# Data.net
KiCad netlist of a schematic drawn in Altium Designer
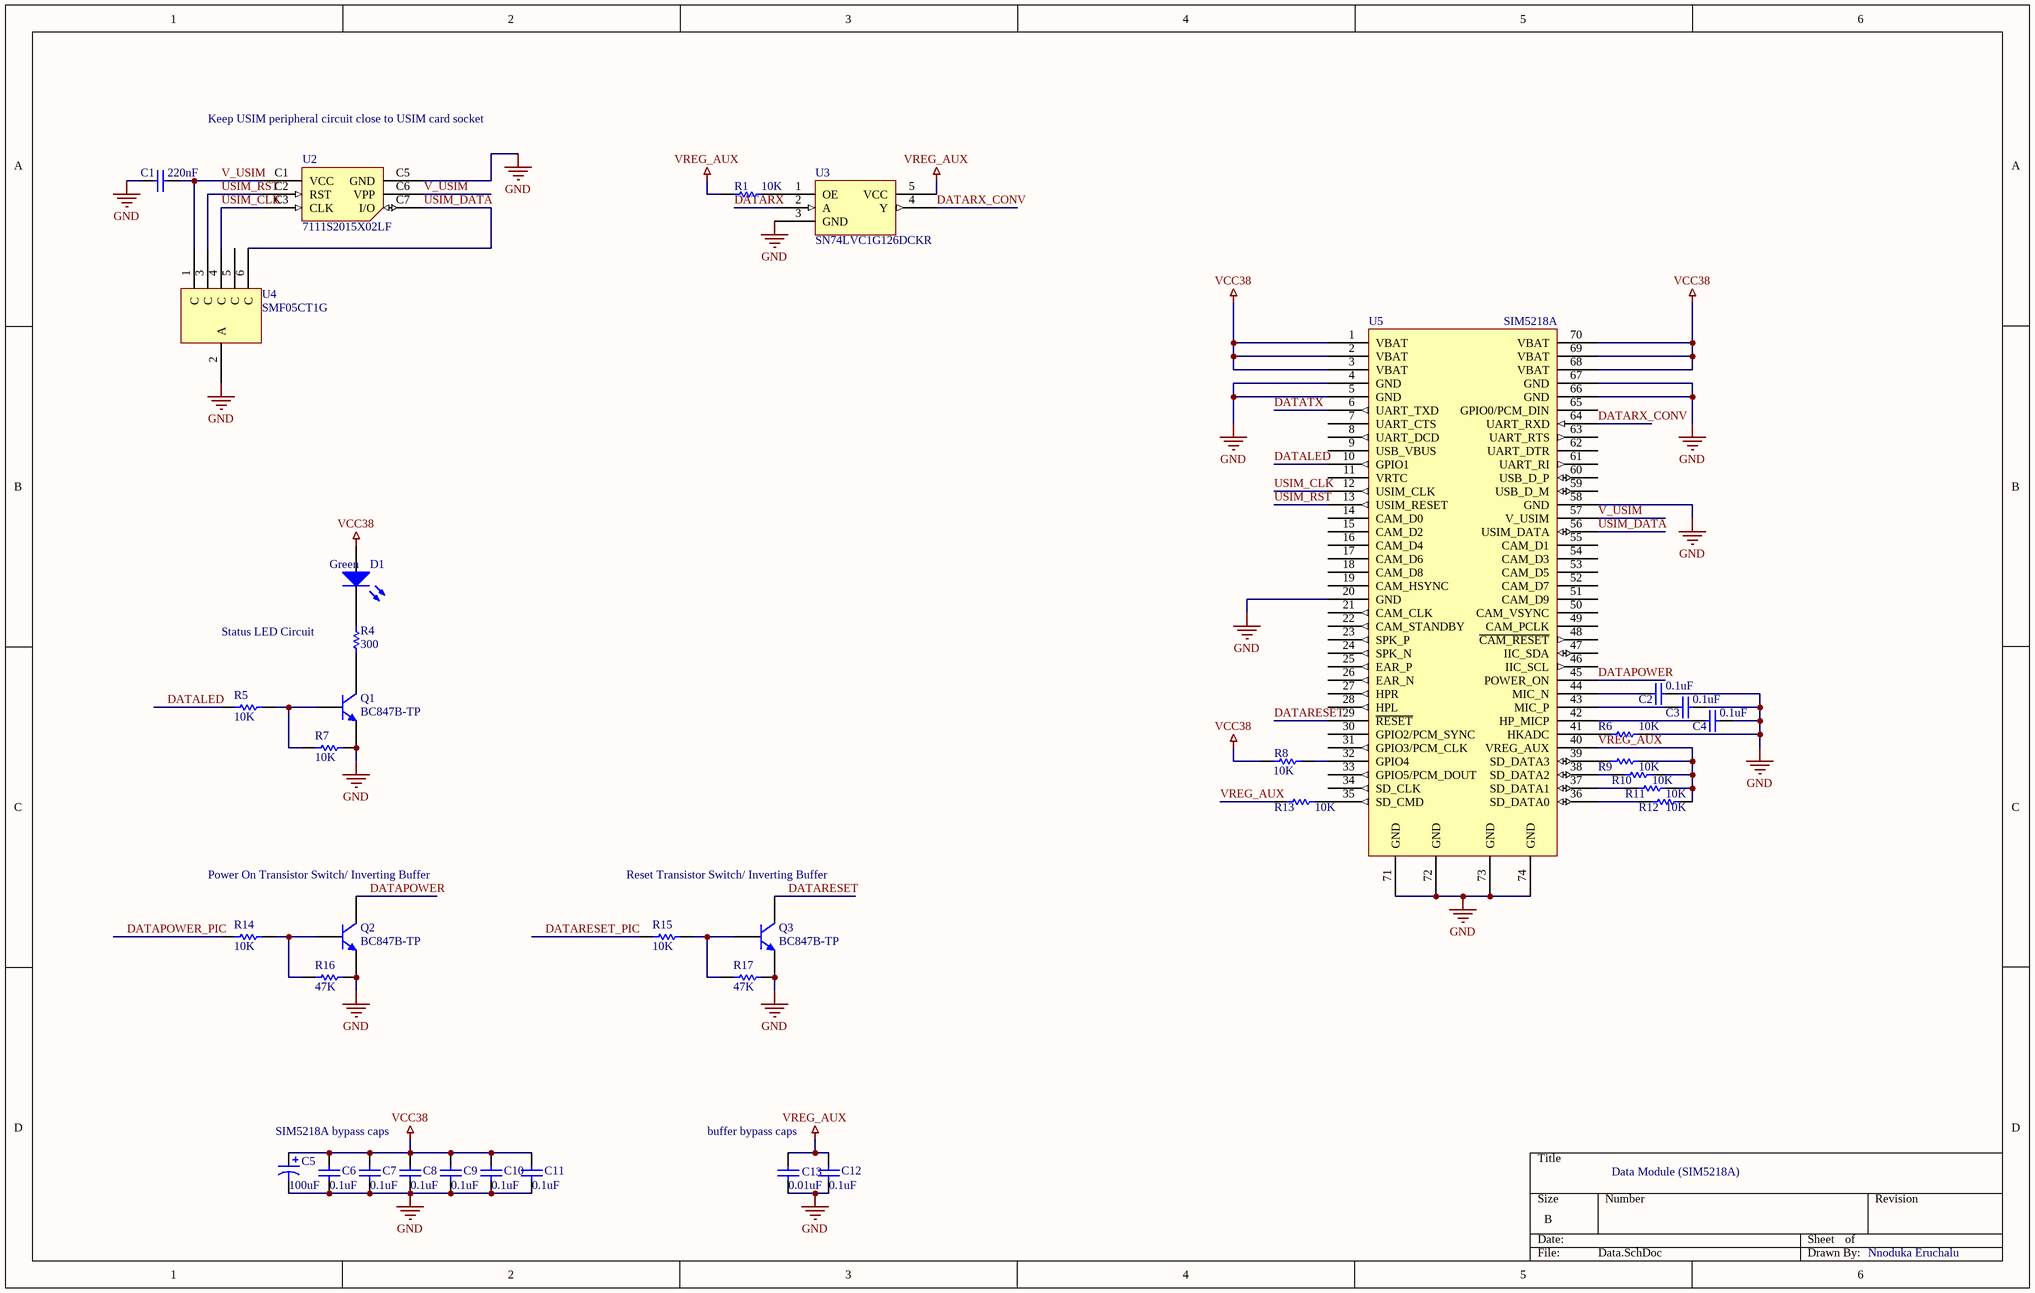
[diagram p0: Data.SchDoc]

(export (version "E")
  (design (tool "Eeschema 10.0.6"))
  (components
    (comp (ref "C1")
      (value "220nF")
      (footprint "2012[0805]")
      (description "Ceramic Chip Capacitor - Standard")
      (fields (field (name "Comment") "C2012X7R1H224K") (field (name "PUBLISHER") "Altium Limited"))
      (libsource (lib "KEMET Chip Capacitor") (part "C0805"))
    )
    (comp (ref "C2")
      (value "0.1uF")
      (footprint "2012[0805]")
      (description "Ceramic Chip Capacitor - Standard")
      (fields (field (name "Comment") "C2012X7R1H104K/0.85") (field (name "PUBLISHER") "Altium Limited"))
      (libsource (lib "KEMET Chip Capacitor") (part "C0805"))
    )
    (comp (ref "C3")
      (value "0.1uF")
      (footprint "2012[0805]")
      (description "Ceramic Chip Capacitor - Standard")
      (fields (field (name "Comment") "C2012X7R1H104K/0.85") (field (name "PUBLISHER") "Altium Limited"))
      (libsource (lib "KEMET Chip Capacitor") (part "C0805"))
    )
    (comp (ref "C4")
      (value "0.1uF")
      (footprint "2012[0805]")
      (description "Ceramic Chip Capacitor - Standard")
      (fields (field (name "Comment") "C2012X7R1H104K/0.85") (field (name "PUBLISHER") "Altium Limited"))
      (libsource (lib "KEMET Chip Capacitor") (part "C0805"))
    )
    (comp (ref "C5")
      (value "100uF")
      (footprint "easypay:TC3528-1411")
      (description "Polarized Capacitor (Radial)")
      (fields (field (name "Comment") "T520B107M004ATE070") (field (name "PUBLISHER") "Altium Limited"))
      (libsource (lib "Miscellaneous Devices") (part "Cap Pol1"))
    )
    (comp (ref "C6")
      (value "0.1uF")
      (footprint "2012[0805]")
      (description "Ceramic Chip Capacitor - Standard")
      (fields (field (name "Comment") "C2012X7R1H104K/0.85") (field (name "PUBLISHER") "Altium Limited"))
      (libsource (lib "KEMET Chip Capacitor") (part "C0805"))
    )
    (comp (ref "C7")
      (value "0.1uF")
      (footprint "2012[0805]")
      (description "Ceramic Chip Capacitor - Standard")
      (fields (field (name "Comment") "C2012X7R1H104K/0.85") (field (name "PUBLISHER") "Altium Limited"))
      (libsource (lib "KEMET Chip Capacitor") (part "C0805"))
    )
    (comp (ref "C8")
      (value "0.1uF")
      (footprint "2012[0805]")
      (description "Ceramic Chip Capacitor - Standard")
      (fields (field (name "Comment") "C2012X7R1H104K/0.85") (field (name "PUBLISHER") "Altium Limited"))
      (libsource (lib "KEMET Chip Capacitor") (part "C0805"))
    )
    (comp (ref "C9")
      (value "0.1uF")
      (footprint "2012[0805]")
      (description "Ceramic Chip Capacitor - Standard")
      (fields (field (name "Comment") "C2012X7R1H104K/0.85") (field (name "PUBLISHER") "Altium Limited"))
      (libsource (lib "KEMET Chip Capacitor") (part "C0805"))
    )
    (comp (ref "C10")
      (value "0.1uF")
      (footprint "2012[0805]")
      (description "Ceramic Chip Capacitor - Standard")
      (fields (field (name "Comment") "C2012X7R1H104K/0.85") (field (name "PUBLISHER") "Altium Limited"))
      (libsource (lib "KEMET Chip Capacitor") (part "C0805"))
    )
    (comp (ref "C11")
      (value "0.1uF")
      (footprint "2012[0805]")
      (description "Ceramic Chip Capacitor - Standard")
      (fields (field (name "Comment") "C2012X7R1H104K/0.85") (field (name "PUBLISHER") "Altium Limited"))
      (libsource (lib "KEMET Chip Capacitor") (part "C0805"))
    )
    (comp (ref "C12")
      (value "0.1uF")
      (footprint "2012[0805]")
      (description "Ceramic Chip Capacitor - Standard")
      (fields (field (name "Comment") "C2012X7R1H104K/0.85") (field (name "PUBLISHER") "Altium Limited"))
      (libsource (lib "KEMET Chip Capacitor") (part "C0805"))
    )
    (comp (ref "C13")
      (value "0.01uF")
      (footprint "2012[0805]")
      (description "Ceramic Chip Capacitor - Standard")
      (fields (field (name "Comment") "C2012X7R2E103K") (field (name "PUBLISHER") "Altium Limited"))
      (libsource (lib "KEMET Chip Capacitor") (part "C0805"))
    )
    (comp (ref "D1")
      (value "Green")
      (footprint "LTST-C17X")
      (description "Typical RED, GREEN, YELLOW, AMBER GaAs LED")
      (fields (field (name "Comment") "LTST-C171GKT") (field (name "PUBLISHER") "Altium Limited"))
      (libsource (lib "Miscellaneous Devices") (part "LED2"))
    )
    (comp (ref "Q1")
      (value "BC847B-TP")
      (footprint "SOT23-3N")
      (description "NPN Bipolar Transistor")
      (fields (field (name "PUBLISHER") "Altium Limited"))
      (libsource (lib "Miscellaneous Devices") (part "NPN"))
    )
    (comp (ref "Q2")
      (value "BC847B-TP")
      (footprint "SOT23-3N")
      (description "NPN Bipolar Transistor")
      (fields (field (name "PUBLISHER") "Altium Limited"))
      (libsource (lib "Miscellaneous Devices") (part "NPN"))
    )
    (comp (ref "Q3")
      (value "BC847B-TP")
      (footprint "SOT23-3N")
      (description "NPN Bipolar Transistor")
      (fields (field (name "PUBLISHER") "Altium Limited"))
      (libsource (lib "Miscellaneous Devices") (part "NPN"))
    )
    (comp (ref "R1")
      (value "10K")
      (footprint "Miscellaneous Devices:2012[0805]")
      (description "Resistor")
      (fields (field (name "Comment") "ERJ-6GEYJ103V") (field (name "PUBLISHER") "Altium Limited"))
      (libsource (lib "Miscellaneous Devices") (part "Res1"))
    )
    (comp (ref "R4")
      (value "300")
      (footprint "Miscellaneous Devices:2012[0805]")
      (description "Resistor")
      (fields (field (name "Comment") "ERJ-6GEYJ301V") (field (name "PUBLISHER") "Altium Limited"))
      (libsource (lib "Miscellaneous Devices") (part "Res1"))
    )
    (comp (ref "R5")
      (value "10K")
      (footprint "Miscellaneous Devices:2012[0805]")
      (description "Resistor")
      (fields (field (name "Comment") "ERJ-6GEYJ103V") (field (name "PUBLISHER") "Altium Limited"))
      (libsource (lib "Miscellaneous Devices") (part "Res1"))
    )
    (comp (ref "R6")
      (value "10K")
      (footprint "Miscellaneous Devices:2012[0805]")
      (description "Resistor")
      (fields (field (name "Comment") "ERJ-6GEYJ103V") (field (name "PUBLISHER") "Altium Limited"))
      (libsource (lib "Miscellaneous Devices") (part "Res1"))
    )
    (comp (ref "R7")
      (value "10K")
      (footprint "Miscellaneous Devices:2012[0805]")
      (description "Resistor")
      (fields (field (name "Comment") "ERJ-6GEYJ103V") (field (name "PUBLISHER") "Altium Limited"))
      (libsource (lib "Miscellaneous Devices") (part "Res1"))
    )
    (comp (ref "R8")
      (value "10K")
      (footprint "Miscellaneous Devices:2012[0805]")
      (description "Resistor")
      (fields (field (name "Comment") "ERJ-6GEYJ103V") (field (name "PUBLISHER") "Altium Limited"))
      (libsource (lib "Miscellaneous Devices") (part "Res1"))
    )
    (comp (ref "R9")
      (value "10K")
      (footprint "Miscellaneous Devices:2012[0805]")
      (description "Resistor")
      (fields (field (name "Comment") "ERJ-6GEYJ103V") (field (name "PUBLISHER") "Altium Limited"))
      (libsource (lib "Miscellaneous Devices") (part "Res1"))
    )
    (comp (ref "R10")
      (value "10K")
      (footprint "Miscellaneous Devices:2012[0805]")
      (description "Resistor")
      (fields (field (name "Comment") "ERJ-6GEYJ103V") (field (name "PUBLISHER") "Altium Limited"))
      (libsource (lib "Miscellaneous Devices") (part "Res1"))
    )
    (comp (ref "R11")
      (value "10K")
      (footprint "Miscellaneous Devices:2012[0805]")
      (description "Resistor")
      (fields (field (name "Comment") "ERJ-6GEYJ103V") (field (name "PUBLISHER") "Altium Limited"))
      (libsource (lib "Miscellaneous Devices") (part "Res1"))
    )
    (comp (ref "R12")
      (value "10K")
      (footprint "Miscellaneous Devices:2012[0805]")
      (description "Resistor")
      (fields (field (name "Comment") "ERJ-6GEYJ103V") (field (name "PUBLISHER") "Altium Limited"))
      (libsource (lib "Miscellaneous Devices") (part "Res1"))
    )
    (comp (ref "R13")
      (value "10K")
      (footprint "Miscellaneous Devices:2012[0805]")
      (description "Resistor")
      (fields (field (name "Comment") "ERJ-6GEYJ103V") (field (name "PUBLISHER") "Altium Limited"))
      (libsource (lib "Miscellaneous Devices") (part "Res1"))
    )
    (comp (ref "R14")
      (value "10K")
      (footprint "Miscellaneous Devices:2012[0805]")
      (description "Resistor")
      (fields (field (name "Comment") "ERJ-6GEYJ103V") (field (name "PUBLISHER") "Altium Limited"))
      (libsource (lib "Miscellaneous Devices") (part "Res1"))
    )
    (comp (ref "R15")
      (value "10K")
      (footprint "Miscellaneous Devices:2012[0805]")
      (description "Resistor")
      (fields (field (name "Comment") "ERJ-6GEYJ103V") (field (name "PUBLISHER") "Altium Limited"))
      (libsource (lib "Miscellaneous Devices") (part "Res1"))
    )
    (comp (ref "R16")
      (value "47K")
      (footprint "Miscellaneous Devices:2012[0805]")
      (description "Resistor")
      (fields (field (name "Comment") "ERJ-6GEYJ473V") (field (name "PUBLISHER") "Altium Limited"))
      (libsource (lib "Miscellaneous Devices") (part "Res1"))
    )
    (comp (ref "R17")
      (value "47K")
      (footprint "Miscellaneous Devices:2012[0805]")
      (description "Resistor")
      (fields (field (name "Comment") "ERJ-6GEYJ473V") (field (name "PUBLISHER") "Altium Limited"))
      (libsource (lib "Miscellaneous Devices") (part "Res1"))
    )
    (comp (ref "U2")
      (value "7111S2015X02LF")
      (footprint "7111S2015X02LF")
      (libsource (lib "easypay") (part "7111S2015X02LF"))
    )
    (comp (ref "U3")
      (value "SN74LVC1G126DCKR")
      (footprint "SOT353-5N")
      (libsource (lib "easypay") (part "SN74LVC1G126"))
    )
    (comp (ref "U4") (value "SMF05CT1G") (footprint "SOT363-6N") (libsource (lib "easypay") (part "SMF05C")))
    (comp (ref "U5")
      (value "SIM5218A")
      (footprint "SIM5218A v2")
      (libsource (lib "easypay") (part "SIM5218A"))
    )
  )
  (nets
    (net (code "1") (name "/DATALED") (class "Default")
      (node (ref "R5") (pin "2") (pinfunction "2_2") (pintype "passive"))
      (node (ref "U5") (pin "10") (pinfunction "GPIO1_10") (pintype "output"))
    )
    (net (code "2") (name "/DATAPOWER") (class "Default")
      (node (ref "Q2") (pin "3") (pinfunction "C_3") (pintype "passive"))
      (node (ref "U5") (pin "45") (pinfunction "POWER_ON_45") (pintype "passive"))
    )
    (net (code "3") (name "/DATAPOWER_PIC") (class "Default")
      (node (ref "R14") (pin "2") (pinfunction "2_2") (pintype "passive"))
    )
    (net (code "4") (name "/DATARESET") (class "Default")
      (node (ref "Q3") (pin "3") (pinfunction "C_3") (pintype "passive"))
      (node (ref "U5") (pin "29") (pinfunction "~{RESET}_29") (pintype "passive"))
    )
    (net (code "5") (name "/DATARESET_PIC") (class "Default")
      (node (ref "R15") (pin "2") (pinfunction "2_2") (pintype "passive"))
    )
    (net (code "6") (name "/DATARX") (class "Default")
      (node (ref "U3") (pin "2") (pinfunction "A_2") (pintype "input"))
    )
    (net (code "7") (name "/DATARX_CONV") (class "Default")
      (node (ref "U3") (pin "4") (pinfunction "Y_4") (pintype "output"))
      (node (ref "U5") (pin "64") (pinfunction "UART_RXD_64") (pintype "input"))
    )
    (net (code "8") (name "/DATATX") (class "Default")
      (node (ref "U5") (pin "6") (pinfunction "UART_TXD_6") (pintype "output"))
    )
    (net (code "9") (name "/USIM_CLK") (class "Default")
      (node (ref "U2") (pin "C3") (pinfunction "CLK_C3") (pintype "input"))
      (node (ref "U4") (pin "4") (pinfunction "C_4") (pintype "passive"))
      (node (ref "U5") (pin "12") (pinfunction "USIM_CLK_12") (pintype "output"))
    )
    (net (code "10") (name "/USIM_DATA") (class "Default")
      (node (ref "U2") (pin "C7") (pinfunction "I/O_C7") (pintype "bidirectional"))
      (node (ref "U4") (pin "6") (pinfunction "C_6") (pintype "passive"))
      (node (ref "U5") (pin "56") (pinfunction "USIM_DATA_56") (pintype "bidirectional"))
    )
    (net (code "11") (name "/USIM_RST") (class "Default")
      (node (ref "U2") (pin "C2") (pinfunction "RST_C2") (pintype "input"))
      (node (ref "U4") (pin "3") (pinfunction "C_3") (pintype "passive"))
      (node (ref "U5") (pin "13") (pinfunction "USIM_RESET_13") (pintype "output"))
    )
    (net (code "12") (name "/V_USIM") (class "Default")
      (node (ref "C1") (pin "2") (pinfunction "2_2") (pintype "passive"))
      (node (ref "U2") (pin "C1") (pinfunction "VCC_C1") (pintype "power_in"))
      (node (ref "U2") (pin "C6") (pinfunction "VPP_C6") (pintype "power_in"))
      (node (ref "U4") (pin "1") (pinfunction "C_1") (pintype "passive"))
      (node (ref "U5") (pin "57") (pinfunction "V_USIM_57") (pintype "power_in"))
    )
    (net (code "13") (name "GND") (class "Default")
      (node (ref "C1") (pin "1") (pinfunction "1_1") (pintype "passive"))
      (node (ref "C10") (pin "1") (pinfunction "1_1") (pintype "passive"))
      (node (ref "C11") (pin "1") (pinfunction "1_1") (pintype "passive"))
      (node (ref "C12") (pin "1") (pinfunction "1_1") (pintype "passive"))
      (node (ref "C13") (pin "1") (pinfunction "1_1") (pintype "passive"))
      (node (ref "C2") (pin "2") (pinfunction "2_2") (pintype "passive"))
      (node (ref "C3") (pin "2") (pinfunction "2_2") (pintype "passive"))
      (node (ref "C4") (pin "2") (pinfunction "2_2") (pintype "passive"))
      (node (ref "C5") (pin "2") (pinfunction "2_2") (pintype "passive"))
      (node (ref "C6") (pin "1") (pinfunction "1_1") (pintype "passive"))
      (node (ref "C7") (pin "1") (pinfunction "1_1") (pintype "passive"))
      (node (ref "C8") (pin "1") (pinfunction "1_1") (pintype "passive"))
      (node (ref "C9") (pin "1") (pinfunction "1_1") (pintype "passive"))
      (node (ref "Q1") (pin "2") (pinfunction "E_2") (pintype "passive"))
      (node (ref "Q2") (pin "2") (pinfunction "E_2") (pintype "passive"))
      (node (ref "Q3") (pin "2") (pinfunction "E_2") (pintype "passive"))
      (node (ref "R16") (pin "1") (pinfunction "1_1") (pintype "passive"))
      (node (ref "R17") (pin "1") (pinfunction "1_1") (pintype "passive"))
      (node (ref "R6") (pin "2") (pinfunction "2_2") (pintype "passive"))
      (node (ref "R7") (pin "1") (pinfunction "1_1") (pintype "passive"))
      (node (ref "U2") (pin "C5") (pinfunction "GND_C5") (pintype "power_in"))
      (node (ref "U3") (pin "3") (pinfunction "GND_3") (pintype "power_in"))
      (node (ref "U4") (pin "2") (pinfunction "A_2") (pintype "power_in"))
      (node (ref "U5") (pin "20") (pinfunction "GND_20") (pintype "power_in"))
      (node (ref "U5") (pin "4") (pinfunction "GND_4") (pintype "power_in"))
      (node (ref "U5") (pin "5") (pinfunction "GND_5") (pintype "power_in"))
      (node (ref "U5") (pin "58") (pinfunction "GND_58") (pintype "power_in"))
      (node (ref "U5") (pin "66") (pinfunction "GND_66") (pintype "power_in"))
      (node (ref "U5") (pin "67") (pinfunction "GND_67") (pintype "power_in"))
      (node (ref "U5") (pin "71") (pinfunction "GND_71") (pintype "power_in"))
      (node (ref "U5") (pin "72") (pinfunction "GND_72") (pintype "power_in"))
      (node (ref "U5") (pin "73") (pinfunction "GND_73") (pintype "power_in"))
      (node (ref "U5") (pin "74") (pinfunction "GND_74") (pintype "power_in"))
    )
    (net (code "14") (name "Net-(D1-K)") (class "Default")
      (node (ref "D1") (pin "2") (pinfunction "K_2") (pintype "passive"))
      (node (ref "R4") (pin "1") (pinfunction "1_1") (pintype "passive"))
    )
    (net (code "15") (name "Net-(Q1-B)") (class "Default")
      (node (ref "Q1") (pin "1") (pinfunction "B_1") (pintype "passive"))
      (node (ref "R5") (pin "1") (pinfunction "1_1") (pintype "passive"))
      (node (ref "R7") (pin "2") (pinfunction "2_2") (pintype "passive"))
    )
    (net (code "16") (name "Net-(Q1-C)") (class "Default")
      (node (ref "Q1") (pin "3") (pinfunction "C_3") (pintype "passive"))
      (node (ref "R4") (pin "2") (pinfunction "2_2") (pintype "passive"))
    )
    (net (code "17") (name "Net-(Q2-B)") (class "Default")
      (node (ref "Q2") (pin "1") (pinfunction "B_1") (pintype "passive"))
      (node (ref "R14") (pin "1") (pinfunction "1_1") (pintype "passive"))
      (node (ref "R16") (pin "2") (pinfunction "2_2") (pintype "passive"))
    )
    (net (code "18") (name "Net-(Q3-B)") (class "Default")
      (node (ref "Q3") (pin "1") (pinfunction "B_1") (pintype "passive"))
      (node (ref "R15") (pin "1") (pinfunction "1_1") (pintype "passive"))
      (node (ref "R17") (pin "2") (pinfunction "2_2") (pintype "passive"))
    )
    (net (code "19") (name "Net-(U3-OE)") (class "Default")
      (node (ref "R1") (pin "1") (pinfunction "1_1") (pintype "passive"))
      (node (ref "U3") (pin "1") (pinfunction "OE_1") (pintype "passive"))
    )
    (net (code "20") (name "Net-(U5-GPIO4)") (class "Default")
      (node (ref "R8") (pin "2") (pinfunction "2_2") (pintype "passive"))
      (node (ref "U5") (pin "32") (pinfunction "GPIO4_32") (pintype "passive"))
    )
    (net (code "21") (name "Net-(U5-HKADC)") (class "Default")
      (node (ref "R6") (pin "1") (pinfunction "1_1") (pintype "passive"))
      (node (ref "U5") (pin "41") (pinfunction "HKADC_41") (pintype "passive"))
    )
    (net (code "22") (name "Net-(U5-HP_MICP)") (class "Default")
      (node (ref "C4") (pin "1") (pinfunction "1_1") (pintype "passive"))
      (node (ref "U5") (pin "42") (pinfunction "HP_MICP_42") (pintype "passive"))
    )
    (net (code "23") (name "Net-(U5-MIC_N)") (class "Default")
      (node (ref "C2") (pin "1") (pinfunction "1_1") (pintype "passive"))
      (node (ref "U5") (pin "44") (pinfunction "MIC_N_44") (pintype "passive"))
    )
    (net (code "24") (name "Net-(U5-MIC_P)") (class "Default")
      (node (ref "C3") (pin "1") (pinfunction "1_1") (pintype "passive"))
      (node (ref "U5") (pin "43") (pinfunction "MIC_P_43") (pintype "passive"))
    )
    (net (code "25") (name "Net-(U5-SD_CMD)") (class "Default")
      (node (ref "R13") (pin "2") (pinfunction "2_2") (pintype "passive"))
      (node (ref "U5") (pin "35") (pinfunction "SD_CMD_35") (pintype "output"))
    )
    (net (code "26") (name "Net-(U5-SD_DATA0)") (class "Default")
      (node (ref "R12") (pin "1") (pinfunction "1_1") (pintype "passive"))
      (node (ref "U5") (pin "36") (pinfunction "SD_DATA0_36") (pintype "bidirectional"))
    )
    (net (code "27") (name "Net-(U5-SD_DATA1)") (class "Default")
      (node (ref "R11") (pin "1") (pinfunction "1_1") (pintype "passive"))
      (node (ref "U5") (pin "37") (pinfunction "SD_DATA1_37") (pintype "bidirectional"))
    )
    (net (code "28") (name "Net-(U5-SD_DATA2)") (class "Default")
      (node (ref "R10") (pin "1") (pinfunction "1_1") (pintype "passive"))
      (node (ref "U5") (pin "38") (pinfunction "SD_DATA2_38") (pintype "bidirectional"))
    )
    (net (code "29") (name "Net-(U5-SD_DATA3)") (class "Default")
      (node (ref "R9") (pin "1") (pinfunction "1_1") (pintype "passive"))
      (node (ref "U5") (pin "39") (pinfunction "SD_DATA3_39") (pintype "bidirectional"))
    )
    (net (code "30") (name "VCC38") (class "Default")
      (node (ref "C10") (pin "2") (pinfunction "2_2") (pintype "passive"))
      (node (ref "C11") (pin "2") (pinfunction "2_2") (pintype "passive"))
      (node (ref "C5") (pin "1") (pinfunction "1_1") (pintype "passive"))
      (node (ref "C6") (pin "2") (pinfunction "2_2") (pintype "passive"))
      (node (ref "C7") (pin "2") (pinfunction "2_2") (pintype "passive"))
      (node (ref "C8") (pin "2") (pinfunction "2_2") (pintype "passive"))
      (node (ref "C9") (pin "2") (pinfunction "2_2") (pintype "passive"))
      (node (ref "D1") (pin "1") (pinfunction "A_1") (pintype "passive"))
      (node (ref "R8") (pin "1") (pinfunction "1_1") (pintype "passive"))
      (node (ref "U5") (pin "1") (pinfunction "VBAT_1") (pintype "power_in"))
      (node (ref "U5") (pin "2") (pinfunction "VBAT_2") (pintype "power_in"))
      (node (ref "U5") (pin "3") (pinfunction "VBAT_3") (pintype "power_in"))
      (node (ref "U5") (pin "68") (pinfunction "VBAT_68") (pintype "power_in"))
      (node (ref "U5") (pin "69") (pinfunction "VBAT_69") (pintype "power_in"))
      (node (ref "U5") (pin "70") (pinfunction "VBAT_70") (pintype "power_in"))
    )
    (net (code "31") (name "VREG_AUX") (class "Default")
      (node (ref "C12") (pin "2") (pinfunction "2_2") (pintype "passive"))
      (node (ref "C13") (pin "2") (pinfunction "2_2") (pintype "passive"))
      (node (ref "R1") (pin "2") (pinfunction "2_2") (pintype "passive"))
      (node (ref "R10") (pin "2") (pinfunction "2_2") (pintype "passive"))
      (node (ref "R11") (pin "2") (pinfunction "2_2") (pintype "passive"))
      (node (ref "R12") (pin "2") (pinfunction "2_2") (pintype "passive"))
      (node (ref "R13") (pin "1") (pinfunction "1_1") (pintype "passive"))
      (node (ref "R9") (pin "2") (pinfunction "2_2") (pintype "passive"))
      (node (ref "U3") (pin "5") (pinfunction "VCC_5") (pintype "power_in"))
      (node (ref "U5") (pin "40") (pinfunction "VREG_AUX_40") (pintype "power_in"))
    )
    (net (code "32") (name "unconnected-(U4-C-Pad5)") (class "Default")
      (node (ref "U4") (pin "5") (pinfunction "C_5") (pintype "passive"))
    )
    (net (code "33") (name "unconnected-(U5-CAM_CLK-Pad21)") (class "Default")
      (node (ref "U5") (pin "21") (pinfunction "CAM_CLK_21") (pintype "output"))
    )
    (net (code "34") (name "unconnected-(U5-CAM_D0-Pad14)") (class "Default")
      (node (ref "U5") (pin "14") (pinfunction "CAM_D0_14") (pintype "passive"))
    )
    (net (code "35") (name "unconnected-(U5-CAM_D1-Pad55)") (class "Default")
      (node (ref "U5") (pin "55") (pinfunction "CAM_D1_55") (pintype "passive"))
    )
    (net (code "36") (name "unconnected-(U5-CAM_D2-Pad15)") (class "Default")
      (node (ref "U5") (pin "15") (pinfunction "CAM_D2_15") (pintype "passive"))
    )
    (net (code "37") (name "unconnected-(U5-CAM_D3-Pad54)") (class "Default")
      (node (ref "U5") (pin "54") (pinfunction "CAM_D3_54") (pintype "passive"))
    )
    (net (code "38") (name "unconnected-(U5-CAM_D4-Pad16)") (class "Default")
      (node (ref "U5") (pin "16") (pinfunction "CAM_D4_16") (pintype "passive"))
    )
    (net (code "39") (name "unconnected-(U5-CAM_D5-Pad53)") (class "Default")
      (node (ref "U5") (pin "53") (pinfunction "CAM_D5_53") (pintype "passive"))
    )
    (net (code "40") (name "unconnected-(U5-CAM_D6-Pad17)") (class "Default")
      (node (ref "U5") (pin "17") (pinfunction "CAM_D6_17") (pintype "passive"))
    )
    (net (code "41") (name "unconnected-(U5-CAM_D7-Pad52)") (class "Default")
      (node (ref "U5") (pin "52") (pinfunction "CAM_D7_52") (pintype "passive"))
    )
    (net (code "42") (name "unconnected-(U5-CAM_D8-Pad18)") (class "Default")
      (node (ref "U5") (pin "18") (pinfunction "CAM_D8_18") (pintype "passive"))
    )
    (net (code "43") (name "unconnected-(U5-CAM_D9-Pad51)") (class "Default")
      (node (ref "U5") (pin "51") (pinfunction "CAM_D9_51") (pintype "passive"))
    )
    (net (code "44") (name "unconnected-(U5-CAM_HSYNC-Pad19)") (class "Default")
      (node (ref "U5") (pin "19") (pinfunction "CAM_HSYNC_19") (pintype "passive"))
    )
    (net (code "45") (name "unconnected-(U5-CAM_PCLK-Pad49)") (class "Default")
      (node (ref "U5") (pin "49") (pinfunction "CAM_PCLK_49") (pintype "passive"))
    )
    (net (code "46") (name "unconnected-(U5-CAM_STANDBY-Pad22)") (class "Default")
      (node (ref "U5") (pin "22") (pinfunction "CAM_STANDBY_22") (pintype "output"))
    )
    (net (code "47") (name "unconnected-(U5-CAM_VSYNC-Pad50)") (class "Default")
      (node (ref "U5") (pin "50") (pinfunction "CAM_VSYNC_50") (pintype "passive"))
    )
    (net (code "48") (name "unconnected-(U5-EAR_N-Pad26)") (class "Default")
      (node (ref "U5") (pin "26") (pinfunction "EAR_N_26") (pintype "output"))
    )
    (net (code "49") (name "unconnected-(U5-EAR_P-Pad25)") (class "Default")
      (node (ref "U5") (pin "25") (pinfunction "EAR_P_25") (pintype "output"))
    )
    (net (code "50") (name "unconnected-(U5-GPIO0{slash}PCM_DIN-Pad65)") (class "Default")
      (node (ref "U5") (pin "65") (pinfunction "GPIO0/PCM_DIN_65") (pintype "passive"))
    )
    (net (code "51") (name "unconnected-(U5-GPIO2{slash}PCM_SYNC-Pad30)") (class "Default")
      (node (ref "U5") (pin "30") (pinfunction "GPIO2/PCM_SYNC_30") (pintype "passive"))
    )
    (net (code "52") (name "unconnected-(U5-GPIO3{slash}PCM_CLK-Pad31)") (class "Default")
      (node (ref "U5") (pin "31") (pinfunction "GPIO3/PCM_CLK_31") (pintype "output"))
    )
    (net (code "53") (name "unconnected-(U5-GPIO5{slash}PCM_DOUT-Pad33)") (class "Default")
      (node (ref "U5") (pin "33") (pinfunction "GPIO5/PCM_DOUT_33") (pintype "output"))
    )
    (net (code "54") (name "unconnected-(U5-HPL-Pad28)") (class "Default")
      (node (ref "U5") (pin "28") (pinfunction "HPL_28") (pintype "output"))
    )
    (net (code "55") (name "unconnected-(U5-HPR-Pad27)") (class "Default")
      (node (ref "U5") (pin "27") (pinfunction "HPR_27") (pintype "output"))
    )
    (net (code "56") (name "unconnected-(U5-IIC_SCL-Pad46)") (class "Default")
      (node (ref "U5") (pin "46") (pinfunction "IIC_SCL_46") (pintype "output"))
    )
    (net (code "57") (name "unconnected-(U5-IIC_SDA-Pad47)") (class "Default")
      (node (ref "U5") (pin "47") (pinfunction "IIC_SDA_47") (pintype "bidirectional"))
    )
    (net (code "58") (name "unconnected-(U5-SD_CLK-Pad34)") (class "Default")
      (node (ref "U5") (pin "34") (pinfunction "SD_CLK_34") (pintype "output"))
    )
    (net (code "59") (name "unconnected-(U5-SPK_N-Pad24)") (class "Default")
      (node (ref "U5") (pin "24") (pinfunction "SPK_N_24") (pintype "output"))
    )
    (net (code "60") (name "unconnected-(U5-SPK_P-Pad23)") (class "Default")
      (node (ref "U5") (pin "23") (pinfunction "SPK_P_23") (pintype "output"))
    )
    (net (code "61") (name "unconnected-(U5-UART_CTS-Pad7)") (class "Default")
      (node (ref "U5") (pin "7") (pinfunction "UART_CTS_7") (pintype "passive"))
    )
    (net (code "62") (name "unconnected-(U5-UART_DCD-Pad8)") (class "Default")
      (node (ref "U5") (pin "8") (pinfunction "UART_DCD_8") (pintype "output"))
    )
    (net (code "63") (name "unconnected-(U5-UART_DTR-Pad62)") (class "Default")
      (node (ref "U5") (pin "62") (pinfunction "UART_DTR_62") (pintype "passive"))
    )
    (net (code "64") (name "unconnected-(U5-UART_RI-Pad61)") (class "Default")
      (node (ref "U5") (pin "61") (pinfunction "UART_RI_61") (pintype "output"))
    )
    (net (code "65") (name "unconnected-(U5-UART_RTS-Pad63)") (class "Default")
      (node (ref "U5") (pin "63") (pinfunction "UART_RTS_63") (pintype "output"))
    )
    (net (code "66") (name "unconnected-(U5-USB_D_M-Pad59)") (class "Default")
      (node (ref "U5") (pin "59") (pinfunction "USB_D_M_59") (pintype "bidirectional"))
    )
    (net (code "67") (name "unconnected-(U5-USB_D_P-Pad60)") (class "Default")
      (node (ref "U5") (pin "60") (pinfunction "USB_D_P_60") (pintype "bidirectional"))
    )
    (net (code "68") (name "unconnected-(U5-USB_VBUS-Pad9)") (class "Default")
      (node (ref "U5") (pin "9") (pinfunction "USB_VBUS_9") (pintype "passive"))
    )
    (net (code "69") (name "unconnected-(U5-VRTC-Pad11)") (class "Default")
      (node (ref "U5") (pin "11") (pinfunction "VRTC_11") (pintype "power_in"))
    )
    (net (code "70") (name "unconnected-(U5-~{CAM_RESET}-Pad48)") (class "Default")
      (node (ref "U5") (pin "48") (pinfunction "~{CAM_RESET}_48") (pintype "output"))
    )
  )
)
